# lipo_alarm.net
KiCad netlist of a schematic drawn in Altium Designer
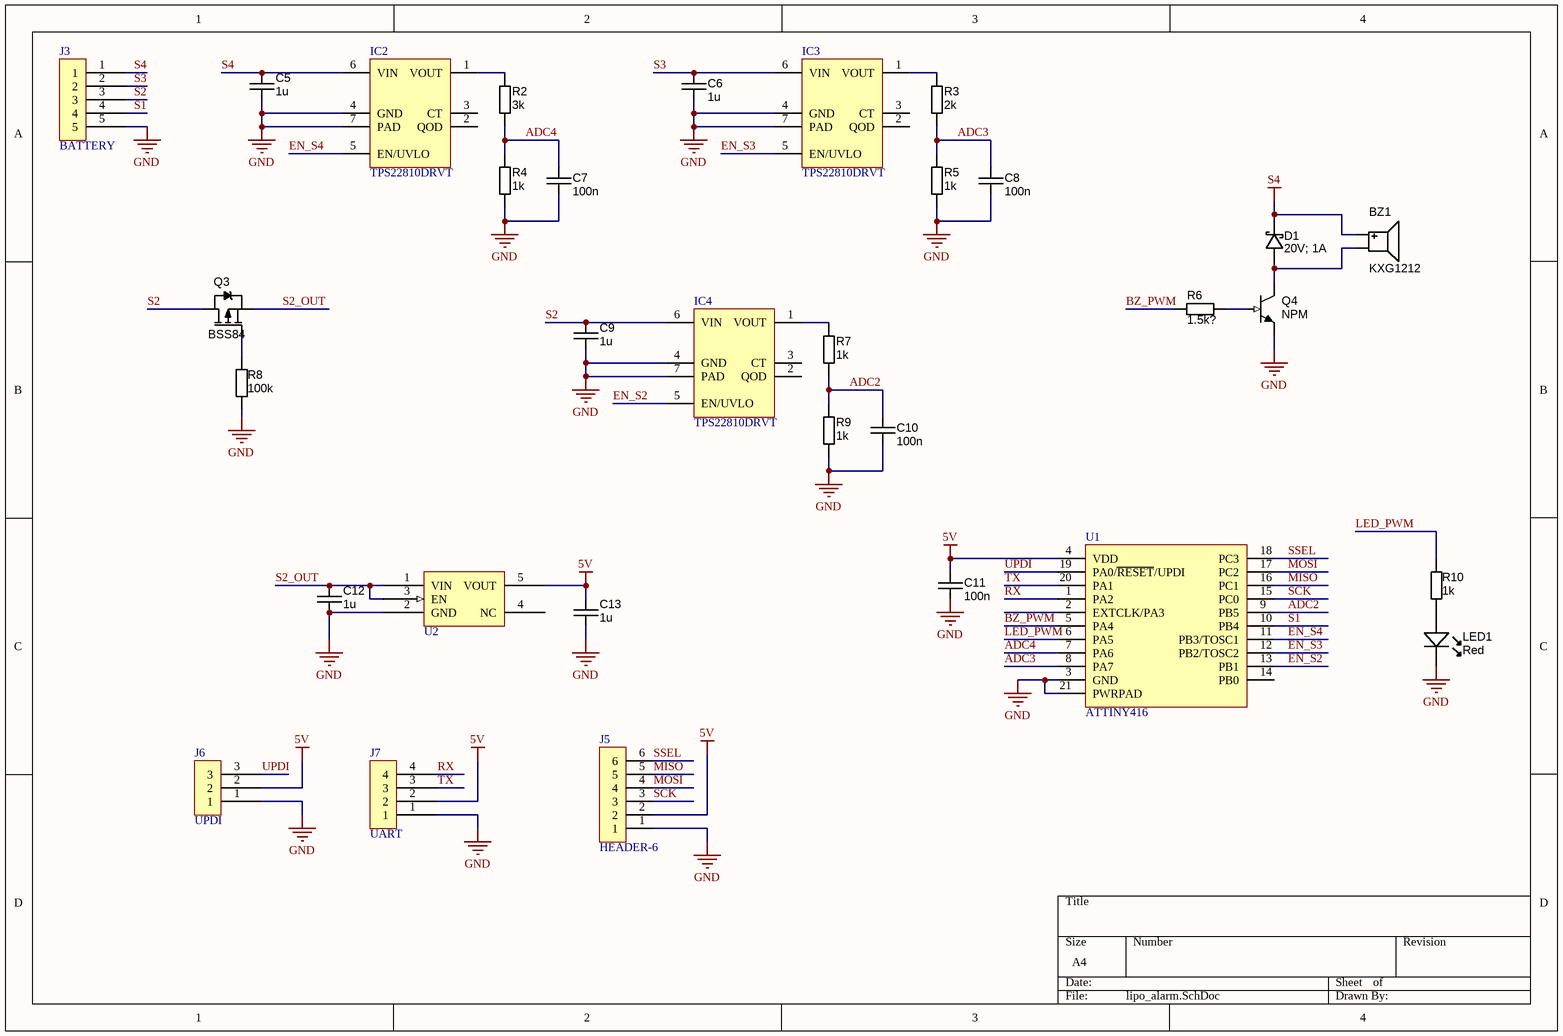
[diagram p0: lipo_alarm.SchDoc]

(export (version "E")
  (design (tool "Eeschema 10.0.6"))
  (components
    (comp (ref "BZ1") (value "KXG1212") (footprint "KXG1212") (libsource (lib "misc") (part "BUZZER")))
    (comp (ref "C5")
      (value "1u")
      (footprint "CAPC1608X90N")
      (description "Capacitor SMD Cer 1uF 10% 16V X7R 0603")
      (fields (field (name "TOLERANCE") "±10%"))
      (libsource (lib "PBL - Capacitors") (part "CAPC_1u_0603_X7R_16V_10%"))
    )
    (comp (ref "C6")
      (value "1u")
      (footprint "CAPC1608X90N")
      (description "Capacitor SMD Cer 1uF 10% 50V X7R 0603")
      (fields (field (name "TOLERANCE") "±10%"))
      (libsource (lib "PBL - Capacitors") (part "CAPC_100n_0603_X7R_50V_10%"))
    )
    (comp (ref "C7")
      (value "100n")
      (footprint "CAPC1608X90N")
      (description "Capacitor SMD Cer 100nF 10% 50V X7R 0603")
      (fields (field (name "TOLERANCE") "±10%"))
      (libsource (lib "PBL - Capacitors") (part "CAPC_100n_0603_X7R_50V_10%"))
    )
    (comp (ref "C8")
      (value "100n")
      (footprint "CAPC1608X90N")
      (description "Capacitor SMD Cer 100nF 10% 50V X7R 0603")
      (fields (field (name "TOLERANCE") "±10%"))
      (libsource (lib "PBL - Capacitors") (part "CAPC_100n_0603_X7R_50V_10%"))
    )
    (comp (ref "C9")
      (value "1u")
      (footprint "CAPC1608X90N")
      (description "Capacitor SMD Cer 1uF 10% 16V X7R 0603")
      (fields (field (name "TOLERANCE") "±10%"))
      (libsource (lib "PBL - Capacitors") (part "CAPC_1u_0603_X7R_16V_10%"))
    )
    (comp (ref "C10")
      (value "100n")
      (footprint "CAPC1608X90N")
      (description "Capacitor SMD Cer 100nF 10% 50V X7R 0603")
      (fields (field (name "TOLERANCE") "±10%"))
      (libsource (lib "PBL - Capacitors") (part "CAPC_100n_0603_X7R_50V_10%"))
    )
    (comp (ref "C11")
      (value "100n")
      (footprint "CAPC1608X90N")
      (description "Capacitor SMD Cer 100nF 10% 50V X7R 0603")
      (fields (field (name "TOLERANCE") "±10%"))
      (libsource (lib "PBL - Capacitors") (part "CAPC_100n_0603_X7R_50V_10%"))
    )
    (comp (ref "C12")
      (value "1u")
      (footprint "CAPC1608X90N")
      (description "Capacitor SMD Cer 2.2uF 10% 10V X5R 0603")
      (fields (field (name "TOLERANCE") "±10%"))
      (libsource (lib "PBL - Capacitors") (part "CAPC_2u2_0603_10V_10%"))
    )
    (comp (ref "C13")
      (value "1u")
      (footprint "CAPC1608X90N")
      (description "Capacitor SMD Cer 2.2uF 10% 10V X5R 0603")
      (fields (field (name "TOLERANCE") "±10%"))
      (libsource (lib "PBL - Capacitors") (part "CAPC_2u2_0603_10V_10%"))
    )
    (comp (ref "D1")
      (value "20V; 1A")
      (footprint "SOD123")
      (description "Diode Schottky SMD 20V 1A SOD123")
      (libsource (lib "PBL - Diodes") (part "DIODE_SCHOTTKY_40V_1A"))
    )
    (comp (ref "IC2")
      (value "TPS22810DRVT")
      (footprint "WSON-6")
      (description "Power Load Switch, 18Vin, 3A, 0.079R, WSON-6, High Side,  TPS22810, TEXAS INSTRUMENTS")
      (fields (field (name "MANUFACTURER") "Texas Instruments"))
      (libsource (lib "power") (part "TPS22810DRVT"))
    )
    (comp (ref "IC3")
      (value "TPS22810DRVT")
      (footprint "WSON-6")
      (description "Power Load Switch, 18Vin, 3A, 0.079R, WSON-6, High Side,  TPS22810, TEXAS INSTRUMENTS")
      (fields (field (name "MANUFACTURER") "Texas Instruments"))
      (libsource (lib "power") (part "TPS22810DRVT"))
    )
    (comp (ref "IC4")
      (value "TPS22810DRVT")
      (footprint "WSON-6")
      (description "Power Load Switch, 18Vin, 3A, 0.079R, WSON-6, High Side,  TPS22810, TEXAS INSTRUMENTS")
      (fields (field (name "MANUFACTURER") "Texas Instruments"))
      (libsource (lib "power") (part "TPS22810DRVT"))
    )
    (comp (ref "J3")
      (value "BATTERY")
      (footprint "JST-XH-5-TH-PCB-CUTOUT")
      (libsource (lib "connectors") (part "HEADER-5"))
    )
    (comp (ref "J5")
      (value "HEADER-6")
      (footprint "MICRO-MATCH-FOB-06")
      (libsource (lib "connectors_micromatch") (part "HEADER-6"))
    )
    (comp (ref "J6")
      (value "UPDI")
      (footprint "PADS-3-1020")
      (libsource (lib "connectors") (part "HEADER-3"))
    )
    (comp (ref "J7")
      (value "UART")
      (footprint "PADS-4-1020")
      (libsource (lib "connectors") (part "HEADER-4"))
    )
    (comp (ref "LED1")
      (value "Red")
      (footprint "LED-0805S-SIDELED-2.1X0.6X1.0")
      (description "LED SMD SIDELED Red 630nm 250mcd 0805")
      (fields (field (name "COLOR") "Red"))
      (libsource (lib "PBL - Light Sources") (part "LED_SMD_RED_0805RA_250mcd"))
    )
    (comp (ref "Q3")
      (value "BSS84")
      (footprint "SOT23-3")
      (description "MOSFET SMD P-CH 50V 130mA SOT23-3")
      (libsource (lib "PBL - Transistors") (part "MOSFET_BSS84"))
    )
    (comp (ref "Q4")
      (value "NPM")
      (footprint "SOT23-3")
      (description "Transistor SMD NPN 15V 3A SOT-23")
      (libsource (lib "PBL - Transistors") (part "NPN_FMMT617TA"))
    )
    (comp (ref "R2")
      (value "3k")
      (footprint "RESC1608X55N")
      (description "Resistor SMD chip 1k Ohm 0.1W 5% 0603")
      (fields (field (name "TOLERANCE") "±5%"))
      (libsource (lib "") (part "RES_1K_0603_5%_1"))
    )
    (comp (ref "R3")
      (value "2k")
      (footprint "RESC1608X55N")
      (description "Resistor SMD chip 1k Ohm 0.1W 5% 0603")
      (fields (field (name "TOLERANCE") "±5%"))
      (libsource (lib "") (part "RES_1K_0603_5%_1"))
    )
    (comp (ref "R4")
      (value "1k")
      (footprint "RESC1608X55N")
      (description "Resistor SMD chip 1k Ohm 0.1W 5% 0603")
      (fields (field (name "TOLERANCE") "±5%"))
      (libsource (lib "") (part "RES_1K_0603_5%_1"))
    )
    (comp (ref "R5")
      (value "1k")
      (footprint "RESC1608X55N")
      (description "Resistor SMD chip 1k Ohm 0.1W 5% 0603")
      (fields (field (name "TOLERANCE") "±5%"))
      (libsource (lib "") (part "RES_1K_0603_5%_1"))
    )
    (comp (ref "R6")
      (value "1.5k?")
      (footprint "RESC1608X55N")
      (description "Resistor SMD chip 1k Ohm 0.1W 5% 0603")
      (fields (field (name "TOLERANCE") "±5%"))
      (libsource (lib "PBL - Resistors") (part "RES_1K_0603_5%"))
    )
    (comp (ref "R7")
      (value "1k")
      (footprint "RESC1608X55N")
      (description "Resistor SMD chip 1k Ohm 0.1W 5% 0603")
      (fields (field (name "TOLERANCE") "±5%"))
      (libsource (lib "") (part "RES_1K_0603_5%_1"))
    )
    (comp (ref "R8")
      (value "100k")
      (footprint "RESC1608X55N")
      (description "Resistor SMD chip 1k Ohm 0.1W 5% 0603")
      (fields (field (name "TOLERANCE") "±5%"))
      (libsource (lib "PBL - Resistors") (part "RES_1K_0603_5%"))
    )
    (comp (ref "R9")
      (value "1k")
      (footprint "RESC1608X55N")
      (description "Resistor SMD chip 1k Ohm 0.1W 5% 0603")
      (fields (field (name "TOLERANCE") "±5%"))
      (libsource (lib "") (part "RES_1K_0603_5%_1"))
    )
    (comp (ref "R10")
      (value "1k")
      (footprint "RESC1608X55N")
      (description "Resistor SMD chip 1k Ohm 0.1W 5% 0603")
      (fields (field (name "TOLERANCE") "±5%"))
      (libsource (lib "") (part "RES_1K_0603_5%_1"))
    )
    (comp (ref "U1")
      (value "ATTINY416")
      (footprint "QFN40P300X300X90_HS-21M")
      (libsource (lib "atmel") (part "ATTINY416"))
    )
    (comp (ref "U2")
      (value "LDO-SOT23-5")
      (footprint "SOT23-5")
      (libsource (lib "power") (part "LDO-SOT23-5"))
    )
  )
  (nets
    (net (code "1") (name "/ADC2") (class "Default")
      (node (ref "C10") (pin "1") (pintype "passive"))
      (node (ref "R7") (pin "2") (pinfunction "2_2") (pintype "passive"))
      (node (ref "R9") (pin "1") (pinfunction "1_1") (pintype "passive"))
      (node (ref "U1") (pin "9") (pinfunction "PB5_9") (pintype "passive"))
    )
    (net (code "2") (name "/ADC3") (class "Default")
      (node (ref "C8") (pin "1") (pintype "passive"))
      (node (ref "R3") (pin "2") (pinfunction "2_2") (pintype "passive"))
      (node (ref "R5") (pin "1") (pinfunction "1_1") (pintype "passive"))
      (node (ref "U1") (pin "8") (pinfunction "PA7_8") (pintype "passive"))
    )
    (net (code "3") (name "/ADC4") (class "Default")
      (node (ref "C7") (pin "1") (pintype "passive"))
      (node (ref "R2") (pin "2") (pinfunction "2_2") (pintype "passive"))
      (node (ref "R4") (pin "1") (pinfunction "1_1") (pintype "passive"))
      (node (ref "U1") (pin "7") (pinfunction "PA6_7") (pintype "passive"))
    )
    (net (code "4") (name "/BZ_PWM") (class "Default")
      (node (ref "R6") (pin "1") (pinfunction "1_1") (pintype "passive"))
      (node (ref "U1") (pin "5") (pinfunction "PA4_5") (pintype "passive"))
    )
    (net (code "5") (name "/EN_S2") (class "Default")
      (node (ref "IC4") (pin "5") (pinfunction "EN/UVLO_5") (pintype "passive"))
      (node (ref "U1") (pin "13") (pinfunction "PB1_13") (pintype "passive"))
    )
    (net (code "6") (name "/EN_S3") (class "Default")
      (node (ref "IC3") (pin "5") (pinfunction "EN/UVLO_5") (pintype "passive"))
      (node (ref "U1") (pin "12") (pinfunction "PB2/TOSC2_12") (pintype "passive"))
    )
    (net (code "7") (name "/EN_S4") (class "Default")
      (node (ref "IC2") (pin "5") (pinfunction "EN/UVLO_5") (pintype "passive"))
      (node (ref "U1") (pin "11") (pinfunction "PB3/TOSC1_11") (pintype "passive"))
    )
    (net (code "8") (name "/LED_PWM") (class "Default")
      (node (ref "R10") (pin "1") (pinfunction "1_1") (pintype "passive"))
      (node (ref "U1") (pin "6") (pinfunction "PA5_6") (pintype "passive"))
    )
    (net (code "9") (name "/MISO") (class "Default")
      (node (ref "J5") (pin "5") (pinfunction "5_5") (pintype "passive"))
      (node (ref "U1") (pin "16") (pinfunction "PC1_16") (pintype "passive"))
    )
    (net (code "10") (name "/MOSI") (class "Default")
      (node (ref "J5") (pin "4") (pinfunction "4_4") (pintype "passive"))
      (node (ref "U1") (pin "17") (pinfunction "PC2_17") (pintype "passive"))
    )
    (net (code "11") (name "/RX") (class "Default")
      (node (ref "J7") (pin "4") (pinfunction "4_4") (pintype "passive"))
      (node (ref "U1") (pin "1") (pinfunction "PA2_1") (pintype "passive"))
    )
    (net (code "12") (name "/S1") (class "Default")
      (node (ref "J3") (pin "4") (pinfunction "4_4") (pintype "passive"))
      (node (ref "U1") (pin "10") (pinfunction "PB4_10") (pintype "passive"))
    )
    (net (code "13") (name "/S2") (class "Default")
      (node (ref "C9") (pin "1") (pintype "passive"))
      (node (ref "IC4") (pin "6") (pinfunction "VIN_6") (pintype "passive"))
      (node (ref "J3") (pin "3") (pinfunction "3_3") (pintype "passive"))
      (node (ref "Q3") (pin "3") (pinfunction "D_3") (pintype "passive"))
    )
    (net (code "14") (name "/S2_OUT") (class "Default")
      (node (ref "C12") (pin "1") (pintype "passive"))
      (node (ref "Q3") (pin "2") (pinfunction "S_2") (pintype "passive"))
      (node (ref "U2") (pin "1") (pinfunction "VIN_1") (pintype "power_in"))
      (node (ref "U2") (pin "3") (pinfunction "EN_3") (pintype "input"))
    )
    (net (code "15") (name "/S3") (class "Default")
      (node (ref "C6") (pin "1") (pintype "passive"))
      (node (ref "IC3") (pin "6") (pinfunction "VIN_6") (pintype "passive"))
      (node (ref "J3") (pin "2") (pinfunction "2_2") (pintype "passive"))
    )
    (net (code "16") (name "/SCK") (class "Default")
      (node (ref "J5") (pin "3") (pinfunction "3_3") (pintype "passive"))
      (node (ref "U1") (pin "15") (pinfunction "PC0_15") (pintype "passive"))
    )
    (net (code "17") (name "/SSEL") (class "Default")
      (node (ref "J5") (pin "6") (pinfunction "6_6") (pintype "passive"))
      (node (ref "U1") (pin "18") (pinfunction "PC3_18") (pintype "passive"))
    )
    (net (code "18") (name "/TX") (class "Default")
      (node (ref "J7") (pin "3") (pinfunction "3_3") (pintype "passive"))
      (node (ref "U1") (pin "20") (pinfunction "PA1_20") (pintype "passive"))
    )
    (net (code "19") (name "/UPDI") (class "Default")
      (node (ref "J6") (pin "3") (pinfunction "3_3") (pintype "passive"))
      (node (ref "U1") (pin "19") (pinfunction "PA0/~{RESET}/UPDI_19") (pintype "passive"))
    )
    (net (code "20") (name "5V") (class "Default")
      (node (ref "C11") (pin "1") (pintype "passive"))
      (node (ref "C13") (pin "1") (pintype "passive"))
      (node (ref "J5") (pin "2") (pinfunction "2_2") (pintype "passive"))
      (node (ref "J6") (pin "2") (pinfunction "2_2") (pintype "passive"))
      (node (ref "J7") (pin "2") (pinfunction "2_2") (pintype "passive"))
      (node (ref "U1") (pin "4") (pinfunction "VDD_4") (pintype "passive"))
      (node (ref "U2") (pin "5") (pinfunction "VOUT_5") (pintype "passive"))
    )
    (net (code "21") (name "GND") (class "Default")
      (node (ref "C10") (pin "2") (pintype "passive"))
      (node (ref "C11") (pin "2") (pintype "passive"))
      (node (ref "C12") (pin "2") (pintype "passive"))
      (node (ref "C13") (pin "2") (pintype "passive"))
      (node (ref "C5") (pin "2") (pintype "passive"))
      (node (ref "C6") (pin "2") (pintype "passive"))
      (node (ref "C7") (pin "2") (pintype "passive"))
      (node (ref "C8") (pin "2") (pintype "passive"))
      (node (ref "C9") (pin "2") (pintype "passive"))
      (node (ref "IC2") (pin "4") (pinfunction "GND_4") (pintype "passive"))
      (node (ref "IC2") (pin "7") (pinfunction "PAD_7") (pintype "passive"))
      (node (ref "IC3") (pin "4") (pinfunction "GND_4") (pintype "passive"))
      (node (ref "IC3") (pin "7") (pinfunction "PAD_7") (pintype "passive"))
      (node (ref "IC4") (pin "4") (pinfunction "GND_4") (pintype "passive"))
      (node (ref "IC4") (pin "7") (pinfunction "PAD_7") (pintype "passive"))
      (node (ref "J3") (pin "5") (pinfunction "5_5") (pintype "passive"))
      (node (ref "J5") (pin "1") (pinfunction "1_1") (pintype "passive"))
      (node (ref "J6") (pin "1") (pinfunction "1_1") (pintype "passive"))
      (node (ref "J7") (pin "1") (pinfunction "1_1") (pintype "passive"))
      (node (ref "LED1") (pin "K") (pinfunction "K_K") (pintype "passive"))
      (node (ref "Q4") (pin "2") (pinfunction "E_2") (pintype "passive"))
      (node (ref "R4") (pin "2") (pinfunction "2_2") (pintype "passive"))
      (node (ref "R5") (pin "2") (pinfunction "2_2") (pintype "passive"))
      (node (ref "R8") (pin "1") (pinfunction "1_1") (pintype "passive"))
      (node (ref "R9") (pin "2") (pinfunction "2_2") (pintype "passive"))
      (node (ref "U1") (pin "21") (pinfunction "PWRPAD_21") (pintype "passive"))
      (node (ref "U1") (pin "3") (pinfunction "GND_3") (pintype "passive"))
      (node (ref "U2") (pin "2") (pinfunction "GND_2") (pintype "power_in"))
    )
    (net (code "22") (name "Net-(BZ1-Negative)") (class "Default")
      (node (ref "BZ1") (pin "2") (pinfunction "Negative_2") (pintype "passive"))
      (node (ref "D1") (pin "A") (pinfunction "A_A") (pintype "passive"))
      (node (ref "Q4") (pin "3") (pinfunction "C_3") (pintype "passive"))
    )
    (net (code "23") (name "Net-(IC2-VOUT)") (class "Default")
      (node (ref "IC2") (pin "1") (pinfunction "VOUT_1") (pintype "passive"))
      (node (ref "R2") (pin "1") (pinfunction "1_1") (pintype "passive"))
    )
    (net (code "24") (name "Net-(IC3-VOUT)") (class "Default")
      (node (ref "IC3") (pin "1") (pinfunction "VOUT_1") (pintype "passive"))
      (node (ref "R3") (pin "1") (pinfunction "1_1") (pintype "passive"))
    )
    (net (code "25") (name "Net-(IC4-VOUT)") (class "Default")
      (node (ref "IC4") (pin "1") (pinfunction "VOUT_1") (pintype "passive"))
      (node (ref "R7") (pin "1") (pinfunction "1_1") (pintype "passive"))
    )
    (net (code "26") (name "Net-(LED1-PadA)") (class "Default")
      (node (ref "LED1") (pin "A") (pinfunction "A_A") (pintype "passive"))
      (node (ref "R10") (pin "2") (pinfunction "2_2") (pintype "passive"))
    )
    (net (code "27") (name "Net-(Q3-G)") (class "Default")
      (node (ref "Q3") (pin "1") (pinfunction "G_1") (pintype "passive"))
      (node (ref "R8") (pin "2") (pinfunction "2_2") (pintype "passive"))
    )
    (net (code "28") (name "Net-(Q4-B)") (class "Default")
      (node (ref "Q4") (pin "1") (pinfunction "B_1") (pintype "input"))
      (node (ref "R6") (pin "2") (pinfunction "2_2") (pintype "passive"))
    )
    (net (code "29") (name "S4") (class "Default")
      (node (ref "BZ1") (pin "1") (pinfunction "Positive_1") (pintype "passive"))
      (node (ref "C5") (pin "1") (pintype "passive"))
      (node (ref "D1") (pin "K") (pinfunction "K_K") (pintype "passive"))
      (node (ref "IC2") (pin "6") (pinfunction "VIN_6") (pintype "passive"))
      (node (ref "J3") (pin "1") (pinfunction "1_1") (pintype "passive"))
    )
    (net (code "30") (name "unconnected-(IC2-CT-Pad3)") (class "Default")
      (node (ref "IC2") (pin "3") (pinfunction "CT_3") (pintype "passive"))
    )
    (net (code "31") (name "unconnected-(IC2-QOD-Pad2)") (class "Default")
      (node (ref "IC2") (pin "2") (pinfunction "QOD_2") (pintype "passive"))
    )
    (net (code "32") (name "unconnected-(IC3-CT-Pad3)") (class "Default")
      (node (ref "IC3") (pin "3") (pinfunction "CT_3") (pintype "passive"))
    )
    (net (code "33") (name "unconnected-(IC3-QOD-Pad2)") (class "Default")
      (node (ref "IC3") (pin "2") (pinfunction "QOD_2") (pintype "passive"))
    )
    (net (code "34") (name "unconnected-(IC4-CT-Pad3)") (class "Default")
      (node (ref "IC4") (pin "3") (pinfunction "CT_3") (pintype "passive"))
    )
    (net (code "35") (name "unconnected-(IC4-QOD-Pad2)") (class "Default")
      (node (ref "IC4") (pin "2") (pinfunction "QOD_2") (pintype "passive"))
    )
    (net (code "36") (name "unconnected-(U1-EXTCLK{slash}PA3-Pad2)") (class "Default")
      (node (ref "U1") (pin "2") (pinfunction "EXTCLK/PA3_2") (pintype "passive"))
    )
    (net (code "37") (name "unconnected-(U1-PB0-Pad14)") (class "Default")
      (node (ref "U1") (pin "14") (pinfunction "PB0_14") (pintype "passive"))
    )
    (net (code "38") (name "unconnected-(U2-NC-Pad4)") (class "Default")
      (node (ref "U2") (pin "4") (pinfunction "NC_4") (pintype "power_in"))
    )
  )
)
